# lcheapo-v4.net
KiCad netlist of a schematic drawn in EAGLE
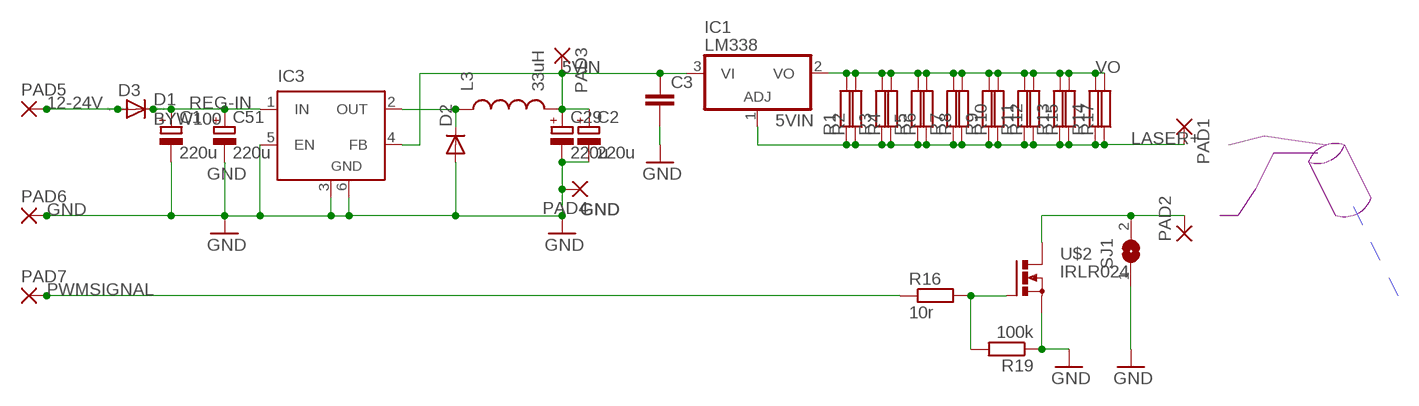
[diagram p0: schematic, sheet 1]

(export (version "E")
  (design (tool "Eeschema 10.0.6"))
  (components
    (comp (ref "C1")
      (value "220u")
      (footprint "eagle-import:E2,5-7")
      (libsource (lib "eagle-import") (part "CPOL-EUE2.5-7"))
    )
    (comp (ref "C2")
      (value "220u")
      (footprint "eagle-import:PANASONIC_D")
      (libsource (lib "eagle-import") (part "CPOL-EUD"))
    )
    (comp (ref "C3")
      (value "C-EUC0603")
      (footprint "eagle-import:C0603")
      (libsource (lib "eagle-import") (part "C-EUC0603"))
    )
    (comp (ref "C29")
      (value "220u")
      (footprint "eagle-import:E2,5-7")
      (libsource (lib "eagle-import") (part "CPOL-EUE2.5-7"))
    )
    (comp (ref "C51")
      (value "220u")
      (footprint "eagle-import:PANASONIC_D")
      (libsource (lib "eagle-import") (part "CPOL-EUD"))
    )
    (comp (ref "D1")
      (value "BYW100")
      (footprint "eagle-import:F126-10")
      (libsource (lib "eagle-import") (part "BYW100"))
    )
    (comp (ref "D2")
      (value "DIODE-DO-214AC")
      (footprint "eagle-import:DO-214AC")
      (libsource (lib "eagle-import") (part "DIODE-DO-214AC"))
    )
    (comp (ref "D3")
      (value "D-SOD-87")
      (footprint "eagle-import:SOD87")
      (libsource (lib "eagle-import") (part "D-SOD-87"))
    )
    (comp (ref "IC1")
      (value "LM338")
      (footprint "eagle-import:TO220H")
      (libsource (lib "eagle-import") (part "317T"))
    )
    (comp (ref "IC3")
      (value "LM2596S")
      (footprint "eagle-import:TO263-5")
      (libsource (lib "eagle-import") (part "LM2596S"))
    )
    (comp (ref "L3")
      (value "33uH")
      (footprint "eagle-import:CDRH125")
      (libsource (lib "eagle-import") (part "INDUCTORPWR"))
    )
    (comp (ref "PAD1")
      (value "2,54/1,0")
      (footprint "eagle-import:2,54_1,0")
      (libsource (lib "eagle-import") (part "2,54/1,0"))
    )
    (comp (ref "PAD2")
      (value "2,54/1,0")
      (footprint "eagle-import:2,54_1,0")
      (libsource (lib "eagle-import") (part "2,54/1,0"))
    )
    (comp (ref "PAD3")
      (value "2,54/1,0")
      (footprint "eagle-import:2,54_1,0")
      (libsource (lib "eagle-import") (part "2,54/1,0"))
    )
    (comp (ref "PAD4")
      (value "2,54/1,0")
      (footprint "eagle-import:2,54_1,0")
      (libsource (lib "eagle-import") (part "2,54/1,0"))
    )
    (comp (ref "PAD5")
      (value "3,17/1,3")
      (footprint "eagle-import:3,17_1,3")
      (libsource (lib "eagle-import") (part "3,17/1,3"))
    )
    (comp (ref "PAD6")
      (value "3,17/1,3")
      (footprint "eagle-import:3,17_1,3")
      (libsource (lib "eagle-import") (part "3,17/1,3"))
    )
    (comp (ref "PAD7")
      (value "2,54/1,0")
      (footprint "eagle-import:2,54_1,0")
      (libsource (lib "eagle-import") (part "2,54/1,0"))
    )
    (comp (ref "R1")
      (value "R-EU_R2512")
      (footprint "eagle-import:R2512")
      (libsource (lib "eagle-import") (part "R-EU_R2512"))
    )
    (comp (ref "R2")
      (value "R-EU_0411/3V")
      (footprint "eagle-import:0411V")
      (libsource (lib "eagle-import") (part "R-EU_0411/3V"))
    )
    (comp (ref "R3")
      (value "R-EU_R2512")
      (footprint "eagle-import:R2512")
      (libsource (lib "eagle-import") (part "R-EU_R2512"))
    )
    (comp (ref "R4")
      (value "R-EU_0411/3V")
      (footprint "eagle-import:0411V")
      (libsource (lib "eagle-import") (part "R-EU_0411/3V"))
    )
    (comp (ref "R5")
      (value "R-EU_R2512")
      (footprint "eagle-import:R2512")
      (libsource (lib "eagle-import") (part "R-EU_R2512"))
    )
    (comp (ref "R6")
      (value "R-EU_0411/3V")
      (footprint "eagle-import:0411V")
      (libsource (lib "eagle-import") (part "R-EU_0411/3V"))
    )
    (comp (ref "R7")
      (value "R-EU_R2512")
      (footprint "eagle-import:R2512")
      (libsource (lib "eagle-import") (part "R-EU_R2512"))
    )
    (comp (ref "R8")
      (value "R-EU_0411/3V")
      (footprint "eagle-import:0411V")
      (libsource (lib "eagle-import") (part "R-EU_0411/3V"))
    )
    (comp (ref "R9")
      (value "R-EU_R2512")
      (footprint "eagle-import:R2512")
      (libsource (lib "eagle-import") (part "R-EU_R2512"))
    )
    (comp (ref "R10")
      (value "R-EU_0411/3V")
      (footprint "eagle-import:0411V")
      (libsource (lib "eagle-import") (part "R-EU_0411/3V"))
    )
    (comp (ref "R11")
      (value "R-EU_R2512")
      (footprint "eagle-import:R2512")
      (libsource (lib "eagle-import") (part "R-EU_R2512"))
    )
    (comp (ref "R12")
      (value "R-EU_0411/3V")
      (footprint "eagle-import:0411V")
      (libsource (lib "eagle-import") (part "R-EU_0411/3V"))
    )
    (comp (ref "R13")
      (value "R-EU_R2512")
      (footprint "eagle-import:R2512")
      (libsource (lib "eagle-import") (part "R-EU_R2512"))
    )
    (comp (ref "R14")
      (value "R-EU_R2512")
      (footprint "eagle-import:R2512")
      (libsource (lib "eagle-import") (part "R-EU_R2512"))
    )
    (comp (ref "R15")
      (value "R-EU_0411/3V")
      (footprint "eagle-import:0411V")
      (libsource (lib "eagle-import") (part "R-EU_0411/3V"))
    )
    (comp (ref "R16")
      (value "10r")
      (footprint "eagle-import:R0603")
      (libsource (lib "eagle-import") (part "R-EU_R0603"))
    )
    (comp (ref "R17")
      (value "R-EU_0411/3V")
      (footprint "eagle-import:0411V")
      (libsource (lib "eagle-import") (part "R-EU_0411/3V"))
    )
    (comp (ref "R19")
      (value "100k")
      (footprint "eagle-import:R0603")
      (libsource (lib "eagle-import") (part "R-EU_R0603"))
    )
    (comp (ref "SJ1") (value "SJ") (footprint "eagle-import:SJ") (libsource (lib "eagle-import") (part "SJ")))
    (comp (ref "U$2")
      (value "IRLR024")
      (footprint "eagle-import:D-PAK_TO252AA")
      (libsource (lib "eagle-import") (part "N-POWER-MOSFETDPAK-MOSFET"))
    )
  )
  (nets
    (net (code "1") (name "/5VIN") (class "Default")
      (node (ref "C2") (pin "+") (pinfunction "+_+") (pintype "passive"))
      (node (ref "C29") (pin "+") (pinfunction "+_+") (pintype "passive"))
      (node (ref "C3") (pin "1") (pinfunction "1_1") (pintype "passive"))
      (node (ref "IC1") (pin "3") (pinfunction "VI_3") (pintype "input"))
      (node (ref "IC3") (pin "4") (pinfunction "FB_4") (pintype "input"))
      (node (ref "L3") (pin "2") (pinfunction "2_2") (pintype "passive"))
      (node (ref "PAD3") (pin "1") (pinfunction "P_1") (pintype "passive"))
    )
    (net (code "2") (name "/12-24V") (class "Default")
      (node (ref "D1") (pin "A") (pinfunction "A_A") (pintype "passive"))
      (node (ref "D3") (pin "2") (pinfunction "A_2") (pintype "passive"))
      (node (ref "PAD5") (pin "1") (pinfunction "P_1") (pintype "passive"))
    )
    (net (code "3") (name "/LASER+") (class "Default")
      (node (ref "IC1") (pin "1") (pinfunction "ADJ_1") (pintype "input"))
      (node (ref "PAD1") (pin "1") (pinfunction "P_1") (pintype "passive"))
      (node (ref "R1") (pin "1") (pinfunction "1_1") (pintype "passive"))
      (node (ref "R10") (pin "1") (pinfunction "1_1") (pintype "passive"))
      (node (ref "R11") (pin "1") (pinfunction "1_1") (pintype "passive"))
      (node (ref "R12") (pin "1") (pinfunction "1_1") (pintype "passive"))
      (node (ref "R13") (pin "1") (pinfunction "1_1") (pintype "passive"))
      (node (ref "R14") (pin "1") (pinfunction "1_1") (pintype "passive"))
      (node (ref "R15") (pin "1") (pinfunction "1_1") (pintype "passive"))
      (node (ref "R17") (pin "1") (pinfunction "1_1") (pintype "passive"))
      (node (ref "R2") (pin "1") (pinfunction "1_1") (pintype "passive"))
      (node (ref "R3") (pin "1") (pinfunction "1_1") (pintype "passive"))
      (node (ref "R4") (pin "1") (pinfunction "1_1") (pintype "passive"))
      (node (ref "R5") (pin "1") (pinfunction "1_1") (pintype "passive"))
      (node (ref "R6") (pin "1") (pinfunction "1_1") (pintype "passive"))
      (node (ref "R7") (pin "1") (pinfunction "1_1") (pintype "passive"))
      (node (ref "R8") (pin "1") (pinfunction "1_1") (pintype "passive"))
      (node (ref "R9") (pin "1") (pinfunction "1_1") (pintype "passive"))
    )
    (net (code "4") (name "/PWMSIGNAL") (class "Default")
      (node (ref "PAD7") (pin "1") (pinfunction "P_1") (pintype "passive"))
      (node (ref "R16") (pin "1") (pinfunction "1_1") (pintype "passive"))
    )
    (net (code "5") (name "/REG-IN") (class "Default")
      (node (ref "C1") (pin "+") (pinfunction "+_+") (pintype "passive"))
      (node (ref "C51") (pin "+") (pinfunction "+_+") (pintype "passive"))
      (node (ref "D1") (pin "C") (pinfunction "C_C") (pintype "passive"))
      (node (ref "D3") (pin "1") (pinfunction "C_1") (pintype "passive"))
      (node (ref "IC3") (pin "1") (pinfunction "IN_1") (pintype "input"))
    )
    (net (code "6") (name "/VO") (class "Default")
      (node (ref "IC1") (pin "2") (pinfunction "VO_2") (pintype "passive"))
      (node (ref "R1") (pin "2") (pinfunction "2_2") (pintype "passive"))
      (node (ref "R10") (pin "2") (pinfunction "2_2") (pintype "passive"))
      (node (ref "R11") (pin "2") (pinfunction "2_2") (pintype "passive"))
      (node (ref "R12") (pin "2") (pinfunction "2_2") (pintype "passive"))
      (node (ref "R13") (pin "2") (pinfunction "2_2") (pintype "passive"))
      (node (ref "R14") (pin "2") (pinfunction "2_2") (pintype "passive"))
      (node (ref "R15") (pin "2") (pinfunction "2_2") (pintype "passive"))
      (node (ref "R17") (pin "2") (pinfunction "2_2") (pintype "passive"))
      (node (ref "R2") (pin "2") (pinfunction "2_2") (pintype "passive"))
      (node (ref "R3") (pin "2") (pinfunction "2_2") (pintype "passive"))
      (node (ref "R4") (pin "2") (pinfunction "2_2") (pintype "passive"))
      (node (ref "R5") (pin "2") (pinfunction "2_2") (pintype "passive"))
      (node (ref "R6") (pin "2") (pinfunction "2_2") (pintype "passive"))
      (node (ref "R7") (pin "2") (pinfunction "2_2") (pintype "passive"))
      (node (ref "R8") (pin "2") (pinfunction "2_2") (pintype "passive"))
      (node (ref "R9") (pin "2") (pinfunction "2_2") (pintype "passive"))
    )
    (net (code "7") (name "GND") (class "Default")
      (node (ref "C1") (pin "-") (pinfunction "-_-") (pintype "passive"))
      (node (ref "C2") (pin "-") (pinfunction "-_-") (pintype "passive"))
      (node (ref "C29") (pin "-") (pinfunction "-_-") (pintype "passive"))
      (node (ref "C3") (pin "2") (pinfunction "2_2") (pintype "passive"))
      (node (ref "C51") (pin "-") (pinfunction "-_-") (pintype "passive"))
      (node (ref "D2") (pin "2") (pinfunction "A_2") (pintype "passive"))
      (node (ref "IC3") (pin "3") (pinfunction "GND_3") (pintype "power_in"))
      (node (ref "IC3") (pin "5") (pinfunction "EN_5") (pintype "input"))
      (node (ref "IC3") (pin "6") (pinfunction "GND_6") (pintype "power_in"))
      (node (ref "PAD4") (pin "1") (pinfunction "P_1") (pintype "passive"))
      (node (ref "PAD6") (pin "1") (pinfunction "P_1") (pintype "passive"))
      (node (ref "R19") (pin "1") (pinfunction "1_1") (pintype "passive"))
      (node (ref "SJ1") (pin "1") (pinfunction "1_1") (pintype "passive"))
      (node (ref "U$2") (pin "3") (pinfunction "S_3") (pintype "passive"))
    )
    (net (code "8") (name "Net-(D2-C)") (class "Default")
      (node (ref "D2") (pin "1") (pinfunction "C_1") (pintype "passive"))
      (node (ref "IC3") (pin "2") (pinfunction "OUT_2") (pintype "output"))
      (node (ref "L3") (pin "1") (pinfunction "1_1") (pintype "passive"))
    )
    (net (code "9") (name "Net-(PAD2-P)") (class "Default")
      (node (ref "PAD2") (pin "1") (pinfunction "P_1") (pintype "passive"))
      (node (ref "SJ1") (pin "2") (pinfunction "2_2") (pintype "passive"))
      (node (ref "U$2") (pin "4") (pinfunction "D_4") (pintype "passive"))
    )
    (net (code "10") (name "Net-(U$2-G)") (class "Default")
      (node (ref "R16") (pin "2") (pinfunction "2_2") (pintype "passive"))
      (node (ref "R19") (pin "2") (pinfunction "2_2") (pintype "passive"))
      (node (ref "U$2") (pin "1") (pinfunction "G_1") (pintype "passive"))
    )
  )
)
